# SparkFun_Pressure_Sensor_BMP581_Qwiic.net
KiCad netlist of a schematic drawn in EAGLE
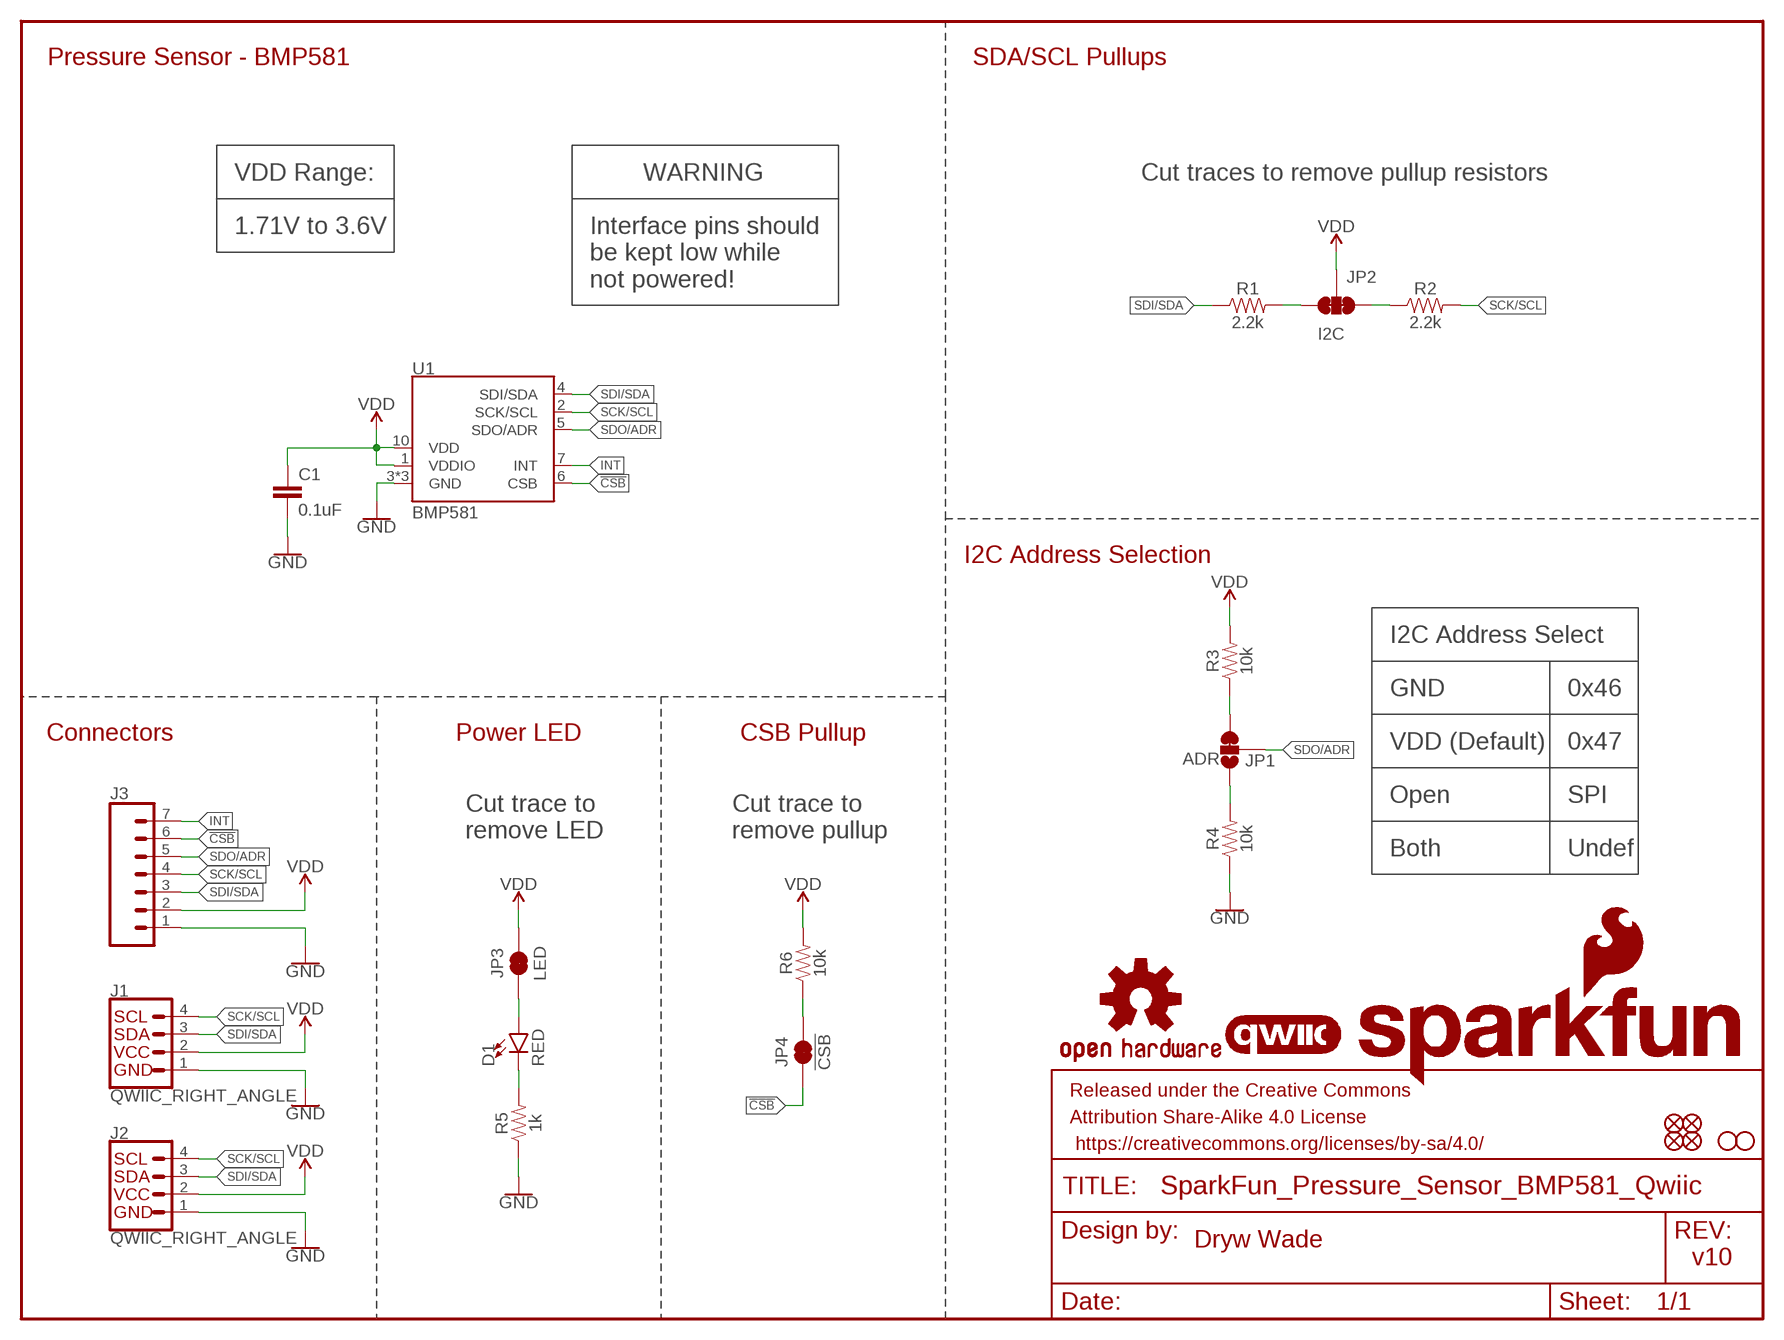
[diagram p0: schematic, sheet 1]

(export (version "E")
  (design (tool "Eeschema 10.0.6"))
  (components
    (comp (ref "C1")
      (value "0.1uF")
      (footprint "eagle-import:0603")
      (libsource (lib "eagle-import") (part "0.1UF-0603-25V-(+80/-20%)"))
    )
    (comp (ref "D1")
      (value "RED")
      (footprint "eagle-import:LED-0603")
      (libsource (lib "eagle-import") (part "LED-RED0603"))
    )
    (comp (ref "FD1")
      (value "FIDUCIAL1X2")
      (footprint "eagle-import:FIDUCIAL-1X2")
      (libsource (lib "eagle-import") (part "FIDUCIAL1X2"))
    )
    (comp (ref "FD2")
      (value "FIDUCIAL1X2")
      (footprint "eagle-import:FIDUCIAL-1X2")
      (libsource (lib "eagle-import") (part "FIDUCIAL1X2"))
    )
    (comp (ref "FD3")
      (value "FIDUCIAL1X2")
      (footprint "eagle-import:FIDUCIAL-1X2")
      (libsource (lib "eagle-import") (part "FIDUCIAL1X2"))
    )
    (comp (ref "FD4")
      (value "FIDUCIAL1X2")
      (footprint "eagle-import:FIDUCIAL-1X2")
      (libsource (lib "eagle-import") (part "FIDUCIAL1X2"))
    )
    (comp (ref "FRAME1")
      (value "FRAME-LETTER")
      (footprint "eagle-import:CREATIVE_COMMONS")
      (libsource (lib "eagle-import") (part "FRAME-LETTER"))
    )
    (comp (ref "H1")
      (value "STAND-OFF")
      (footprint "eagle-import:STAND-OFF")
      (libsource (lib "eagle-import") (part "STAND-OFF"))
    )
    (comp (ref "H2")
      (value "STAND-OFF")
      (footprint "eagle-import:STAND-OFF")
      (libsource (lib "eagle-import") (part "STAND-OFF"))
    )
    (comp (ref "J1")
      (value "QWIIC_RIGHT_ANGLE")
      (footprint "eagle-import:JST04_1MM_RA")
      (libsource (lib "eagle-import") (part "QWIIC_CONNECTORJS-1MM"))
    )
    (comp (ref "J2")
      (value "QWIIC_RIGHT_ANGLE")
      (footprint "eagle-import:JST04_1MM_RA")
      (libsource (lib "eagle-import") (part "QWIIC_CONNECTORJS-1MM"))
    )
    (comp (ref "J3")
      (value "CONN_07NO_SILK")
      (footprint "eagle-import:1X07_NO_SILK")
      (libsource (lib "eagle-import") (part "CONN_07NO_SILK"))
    )
    (comp (ref "JP1")
      (value "ADR")
      (footprint "eagle-import:SMT-JUMPER_3_1-NC_TRACE_SILK")
      (libsource (lib "eagle-import") (part "JUMPER-SMT_3_1-NC_TRACE_SILK"))
    )
    (comp (ref "JP2")
      (value "I2C")
      (footprint "eagle-import:SMT-JUMPER_3_2-NC_TRACE_SILK")
      (libsource (lib "eagle-import") (part "JUMPER-SMT_3_2-NC_TRACE_SILK"))
    )
    (comp (ref "JP3")
      (value "LED")
      (footprint "eagle-import:SMT-JUMPER_2_NC_TRACE_SILK")
      (libsource (lib "eagle-import") (part "JUMPER-SMT_2_NC_TRACE_SILK"))
    )
    (comp (ref "JP4")
      (value "!CSB!")
      (footprint "eagle-import:SMT-JUMPER_2_NC_TRACE_SILK")
      (libsource (lib "eagle-import") (part "JUMPER-SMT_2_NC_TRACE_SILK"))
    )
    (comp (ref "LOGO1")
      (value "OSHW-LOGOS")
      (footprint "eagle-import:OSHW-LOGO-S")
      (libsource (lib "eagle-import") (part "OSHW-LOGOS"))
    )
    (comp (ref "LOGO2")
      (value "SFE_LOGO_FLAME.2_INCH")
      (footprint "eagle-import:SFE_LOGO_FLAME_.2")
      (libsource (lib "eagle-import") (part "SFE_LOGO_FLAME.2_INCH"))
    )
    (comp (ref "LOGO3")
      (value "QWIIC_LOGO_5MM")
      (footprint "eagle-import:QWIIC_5MM")
      (libsource (lib "eagle-import") (part "QWIIC_LOGO_5MM"))
    )
    (comp (ref "LOGO4")
      (value "SFE_LOGO_NAME_FLAME.1_INCH")
      (footprint "eagle-import:SFE_LOGO_NAME_FLAME_.1")
      (libsource (lib "eagle-import") (part "SFE_LOGO_NAME_FLAME.1_INCH"))
    )
    (comp (ref "R1")
      (value "2.2k")
      (footprint "eagle-import:0603")
      (libsource (lib "eagle-import") (part "2.2KOHM-0603-1/10W-1%"))
    )
    (comp (ref "R2")
      (value "2.2k")
      (footprint "eagle-import:0603")
      (libsource (lib "eagle-import") (part "2.2KOHM-0603-1/10W-1%"))
    )
    (comp (ref "R3")
      (value "10k")
      (footprint "eagle-import:0603")
      (libsource (lib "eagle-import") (part "10KOHM-0603-1/10W-1%"))
    )
    (comp (ref "R4")
      (value "10k")
      (footprint "eagle-import:0603")
      (libsource (lib "eagle-import") (part "10KOHM-0603-1/10W-1%"))
    )
    (comp (ref "R5")
      (value "1k")
      (footprint "eagle-import:0603")
      (libsource (lib "eagle-import") (part "1KOHM-0603-1/10W-1%"))
    )
    (comp (ref "R6")
      (value "10k")
      (footprint "eagle-import:0603")
      (libsource (lib "eagle-import") (part "10KOHM-0603-1/10W-1%"))
    )
    (comp (ref "U1")
      (value "BMP581")
      (footprint "eagle-import:BMP581")
      (libsource (lib "eagle-import") (part "BMP581"))
    )
  )
  (nets
    (net (code "1") (name "/~{CSB}") (class "Default")
      (node (ref "J3") (pin "6") (pinfunction "6_6") (pintype "passive"))
      (node (ref "JP4") (pin "1") (pinfunction "1_1") (pintype "passive"))
      (node (ref "U1") (pin "6") (pinfunction "CSB_6") (pintype "input"))
    )
    (net (code "2") (name "GND") (class "Default")
      (node (ref "C1") (pin "2") (pinfunction "2_2") (pintype "passive"))
      (node (ref "J1") (pin "1") (pinfunction "1_1") (pintype "power_in"))
      (node (ref "J2") (pin "1") (pinfunction "1_1") (pintype "power_in"))
      (node (ref "J3") (pin "1") (pinfunction "1_1") (pintype "passive"))
      (node (ref "R4") (pin "1") (pinfunction "1_1") (pintype "passive"))
      (node (ref "R5") (pin "1") (pinfunction "1_1") (pintype "passive"))
      (node (ref "U1") (pin "3") (pinfunction "GND_3") (pintype "power_in"))
      (node (ref "U1") (pin "8") (pinfunction "GND_8") (pintype "power_in"))
      (node (ref "U1") (pin "9") (pinfunction "GND_9") (pintype "power_in"))
    )
    (net (code "3") (name "INT") (class "Default")
      (node (ref "J3") (pin "7") (pinfunction "7_7") (pintype "passive"))
      (node (ref "U1") (pin "7") (pinfunction "INT_7") (pintype "output"))
    )
    (net (code "4") (name "Net-(D1-PadA)") (class "Default")
      (node (ref "D1") (pin "A") (pinfunction "A_A") (pintype "passive"))
      (node (ref "JP3") (pin "1") (pinfunction "1_1") (pintype "passive"))
    )
    (net (code "5") (name "Net-(D1-PadC)") (class "Default")
      (node (ref "D1") (pin "C") (pinfunction "C_C") (pintype "passive"))
      (node (ref "R5") (pin "2") (pinfunction "2_2") (pintype "passive"))
    )
    (net (code "6") (name "Net-(JP1-Pad1)") (class "Default")
      (node (ref "JP1") (pin "1") (pinfunction "1_1") (pintype "passive"))
      (node (ref "R4") (pin "2") (pinfunction "2_2") (pintype "passive"))
    )
    (net (code "7") (name "Net-(JP1-Pad3)") (class "Default")
      (node (ref "JP1") (pin "3") (pinfunction "3_3") (pintype "passive"))
      (node (ref "R3") (pin "1") (pinfunction "1_1") (pintype "passive"))
    )
    (net (code "8") (name "Net-(JP2-Pad1)") (class "Default")
      (node (ref "JP2") (pin "1") (pinfunction "1_1") (pintype "passive"))
      (node (ref "R2") (pin "1") (pinfunction "1_1") (pintype "passive"))
    )
    (net (code "9") (name "Net-(JP2-Pad3)") (class "Default")
      (node (ref "JP2") (pin "3") (pinfunction "3_3") (pintype "passive"))
      (node (ref "R1") (pin "2") (pinfunction "2_2") (pintype "passive"))
    )
    (net (code "10") (name "Net-(JP4-Pad2)") (class "Default")
      (node (ref "JP4") (pin "2") (pinfunction "2_2") (pintype "passive"))
      (node (ref "R6") (pin "1") (pinfunction "1_1") (pintype "passive"))
    )
    (net (code "11") (name "SCK{slash}SCL") (class "Default")
      (node (ref "J1") (pin "4") (pinfunction "4_4") (pintype "passive"))
      (node (ref "J2") (pin "4") (pinfunction "4_4") (pintype "passive"))
      (node (ref "J3") (pin "4") (pinfunction "4_4") (pintype "passive"))
      (node (ref "R2") (pin "2") (pinfunction "2_2") (pintype "passive"))
      (node (ref "U1") (pin "2") (pinfunction "SCK/SCL_2") (pintype "bidirectional"))
    )
    (net (code "12") (name "SDI{slash}SDA") (class "Default")
      (node (ref "J1") (pin "3") (pinfunction "3_3") (pintype "passive"))
      (node (ref "J2") (pin "3") (pinfunction "3_3") (pintype "passive"))
      (node (ref "J3") (pin "3") (pinfunction "3_3") (pintype "passive"))
      (node (ref "R1") (pin "1") (pinfunction "1_1") (pintype "passive"))
      (node (ref "U1") (pin "4") (pinfunction "SDI/SDA_4") (pintype "bidirectional"))
    )
    (net (code "13") (name "SDO{slash}ADR") (class "Default")
      (node (ref "J3") (pin "5") (pinfunction "5_5") (pintype "passive"))
      (node (ref "JP1") (pin "2") (pinfunction "2_2") (pintype "passive"))
      (node (ref "U1") (pin "5") (pinfunction "SDO/ADR_5") (pintype "bidirectional"))
    )
    (net (code "14") (name "VDD") (class "Default")
      (node (ref "C1") (pin "1") (pinfunction "1_1") (pintype "passive"))
      (node (ref "J1") (pin "2") (pinfunction "2_2") (pintype "power_in"))
      (node (ref "J2") (pin "2") (pinfunction "2_2") (pintype "power_in"))
      (node (ref "J3") (pin "2") (pinfunction "2_2") (pintype "passive"))
      (node (ref "JP2") (pin "2") (pinfunction "2_2") (pintype "passive"))
      (node (ref "JP3") (pin "2") (pinfunction "2_2") (pintype "passive"))
      (node (ref "R3") (pin "2") (pinfunction "2_2") (pintype "passive"))
      (node (ref "R6") (pin "2") (pinfunction "2_2") (pintype "passive"))
      (node (ref "U1") (pin "1") (pinfunction "VDDIO_1") (pintype "power_in"))
      (node (ref "U1") (pin "10") (pinfunction "VDD_10") (pintype "power_in"))
    )
  )
)
